# eeZeeProp.net
KiCad netlist of a schematic drawn in EAGLE
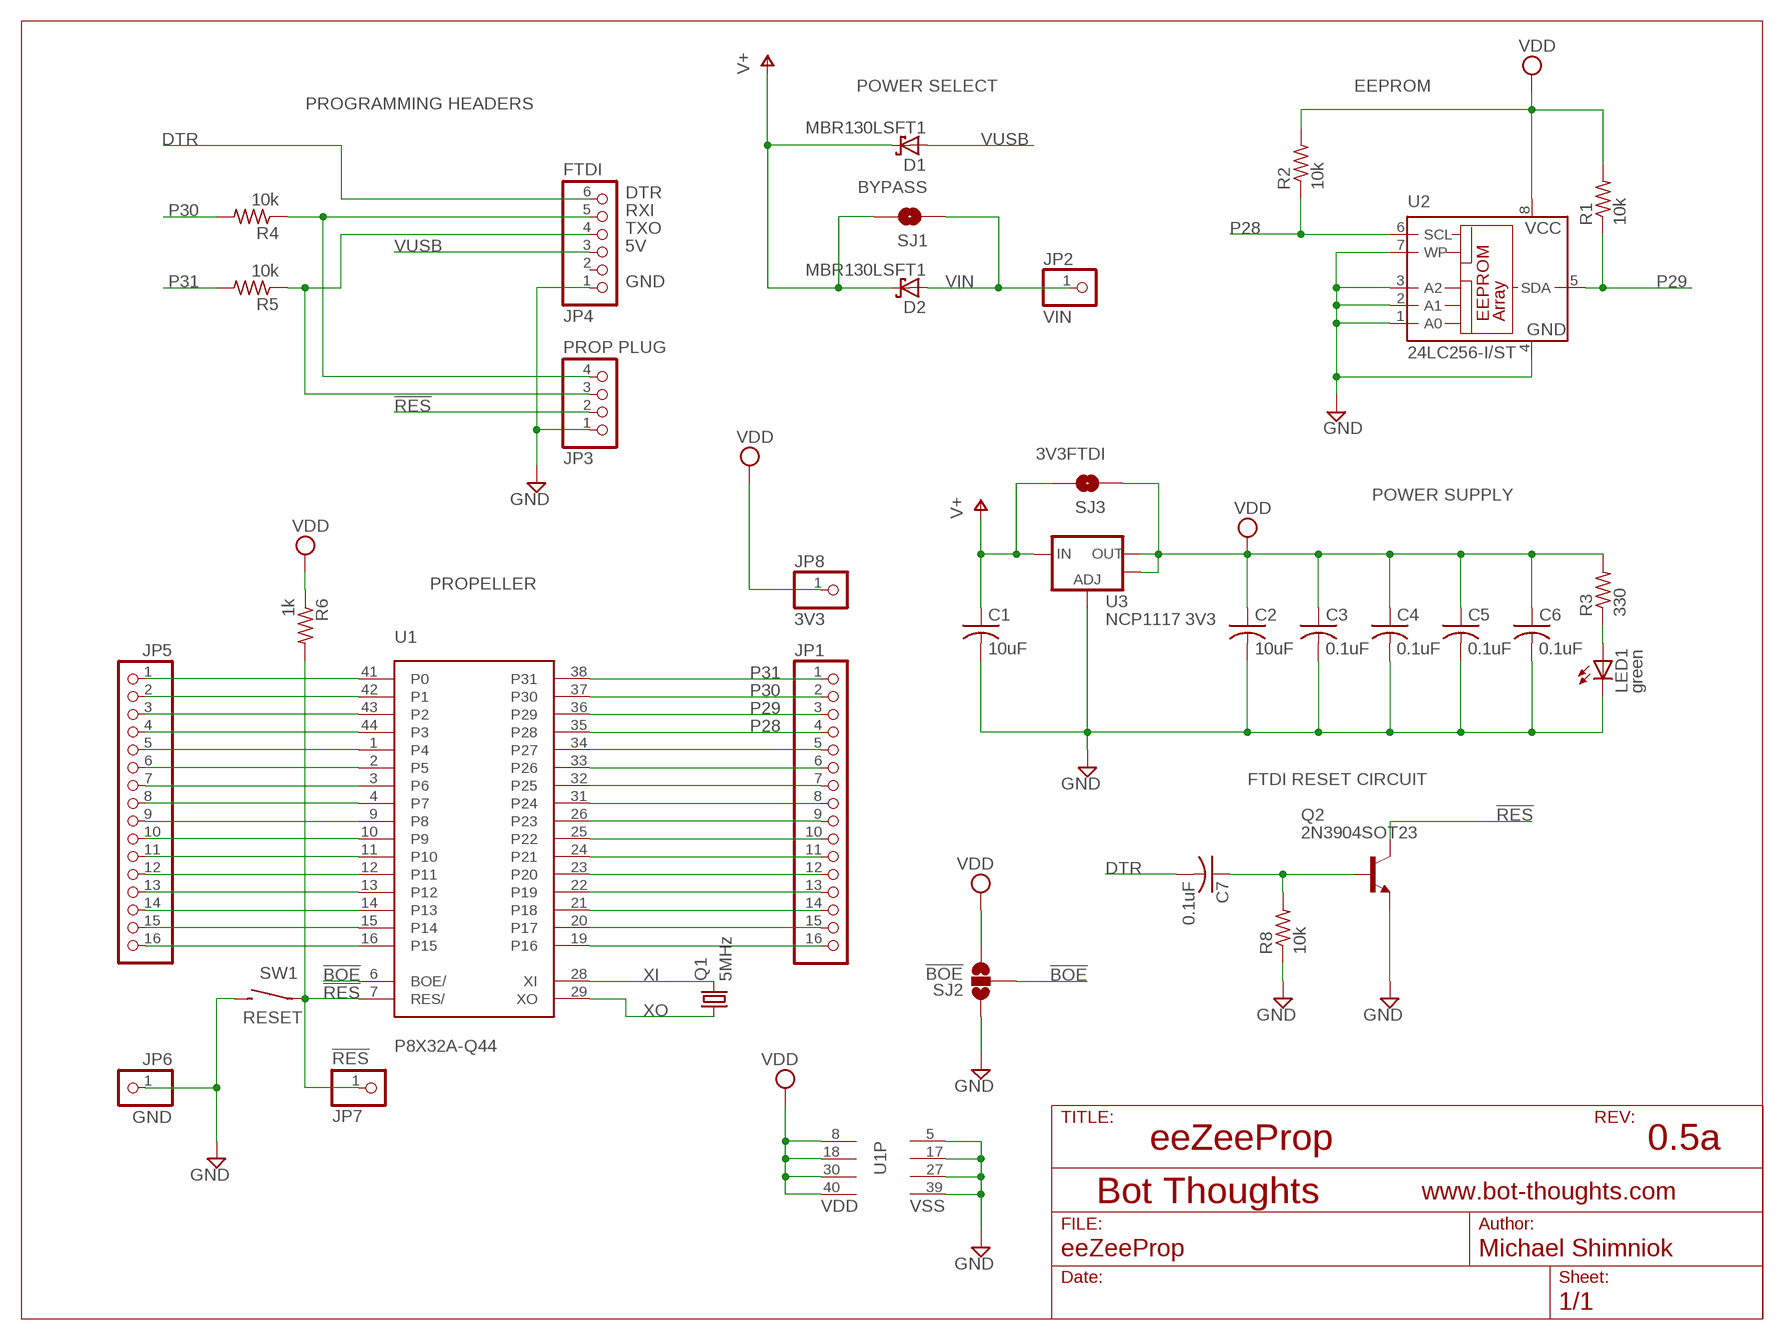
[diagram p0: schematic, sheet 1]

(export (version "E")
  (design (tool "Eeschema 10.0.6"))
  (components
    (comp (ref "C1")
      (value "10uF")
      (footprint "eagle-import:C1206")
      (fields (field (name "PARTNO") "T491A106M006AT"))
      (libsource (lib "eagle-import") (part "C-USC1206"))
    )
    (comp (ref "C2")
      (value "10uF")
      (footprint "eagle-import:C1206")
      (fields (field (name "PARTNO") "T491A106M006AT"))
      (libsource (lib "eagle-import") (part "C-USC1206"))
    )
    (comp (ref "C3")
      (value "0.1uF")
      (footprint "eagle-import:C0603")
      (fields (field (name "PARTNO") "0603YC104KAT2A"))
      (libsource (lib "eagle-import") (part "C-USC0603"))
    )
    (comp (ref "C4")
      (value "0.1uF")
      (footprint "eagle-import:C0603")
      (fields (field (name "PARTNO") "0603YC104KAT2A"))
      (libsource (lib "eagle-import") (part "C-USC0603"))
    )
    (comp (ref "C5")
      (value "0.1uF")
      (footprint "eagle-import:C0603")
      (fields (field (name "PARTNO") "0603YC104KAT2A"))
      (libsource (lib "eagle-import") (part "C-USC0603"))
    )
    (comp (ref "C6")
      (value "0.1uF")
      (footprint "eagle-import:C0603")
      (fields (field (name "PARTNO") "0603YC104KAT2A"))
      (libsource (lib "eagle-import") (part "C-USC0603"))
    )
    (comp (ref "C7")
      (value "0.1uF")
      (footprint "eagle-import:C0603")
      (fields (field (name "PARTNO") "0603YC104KAT2A"))
      (libsource (lib "eagle-import") (part "C-USC0603"))
    )
    (comp (ref "D1")
      (value "MBR130LSFT1")
      (footprint "eagle-import:SOD123FL")
      (fields (field (name "PARTNO") "MBR130LSFT1G"))
      (libsource (lib "eagle-import") (part "SCHOTTKY-DIODE-MBR130LSFT1"))
    )
    (comp (ref "D2")
      (value "MBR130LSFT1")
      (footprint "eagle-import:SOD123FL")
      (fields (field (name "PARTNO") "MBR130LSFT1G"))
      (libsource (lib "eagle-import") (part "SCHOTTKY-DIODE-MBR130LSFT1"))
    )
    (comp (ref "JP1")
      (value "PINHD-1X16_2.54-S")
      (footprint "eagle-import:1X16-S")
      (libsource (lib "eagle-import") (part "PINHD-1X16_2.54-S"))
    )
    (comp (ref "JP2")
      (value "VIN")
      (footprint "eagle-import:1X01")
      (libsource (lib "eagle-import") (part "PINHD-1X01_2.54"))
    )
    (comp (ref "JP3")
      (value "PROP PLUG")
      (footprint "eagle-import:1X04-S")
      (libsource (lib "eagle-import") (part "PINHD-1X04_2.54-S"))
    )
    (comp (ref "JP4")
      (value "FTDI")
      (footprint "eagle-import:1X06-S")
      (fields (field (name "PARTNO") "2211S-06G"))
      (libsource (lib "eagle-import") (part "PINHD-1X06_2.54-S"))
    )
    (comp (ref "JP5")
      (value "PINHD-1X16_2.54-S")
      (footprint "eagle-import:1X16-S")
      (libsource (lib "eagle-import") (part "PINHD-1X16_2.54-S"))
    )
    (comp (ref "JP6")
      (value "GND")
      (footprint "eagle-import:1X01")
      (libsource (lib "eagle-import") (part "PINHD-1X01_2.54"))
    )
    (comp (ref "JP7")
      (value "!RES")
      (footprint "eagle-import:1X01")
      (libsource (lib "eagle-import") (part "PINHD-1X01_2.54"))
    )
    (comp (ref "JP8")
      (value "3V3")
      (footprint "eagle-import:1X01")
      (libsource (lib "eagle-import") (part "PINHD-1X01_2.54"))
    )
    (comp (ref "LED1")
      (value "green")
      (footprint "eagle-import:CHIPLED_1206")
      (fields (field (name "PARTNO") "LG N971-KN-1"))
      (libsource (lib "eagle-import") (part "LEDCHIPLED_1206"))
    )
    (comp (ref "Q1")
      (value "5MHz")
      (footprint "eagle-import:HC49U-V")
      (fields (field (name "OC_FARNELL") "1666969") (field (name "PARTNO") "HC49US-5.000MABJ-UB"))
      (libsource (lib "eagle-import") (part "CRYSTALHC49U-V"))
    )
    (comp (ref "Q2")
      (value "2N3904SOT23")
      (footprint "eagle-import:SOT-23")
      (fields (field (name "PARTNO") "MMBT3904LT3G"))
      (libsource (lib "eagle-import") (part "2N3904SOT23"))
    )
    (comp (ref "R1")
      (value "10k")
      (footprint "eagle-import:R0603")
      (fields (field (name "PARTNO") "ERJ-3GEYJ103V"))
      (libsource (lib "eagle-import") (part "R-US_R0603"))
    )
    (comp (ref "R2")
      (value "10k")
      (footprint "eagle-import:R0603")
      (fields (field (name "PARTNO") "ERJ-3GEYJ103V"))
      (libsource (lib "eagle-import") (part "R-US_R0603"))
    )
    (comp (ref "R3")
      (value "330")
      (footprint "eagle-import:R0603")
      (fields (field (name "PARTNO") "ERJ-3GEYJ331V"))
      (libsource (lib "eagle-import") (part "R-US_R0603"))
    )
    (comp (ref "R4")
      (value "10k")
      (footprint "eagle-import:R0603")
      (fields (field (name "PARTNO") "RC0603JR-071KL"))
      (libsource (lib "eagle-import") (part "R-US_R0603"))
    )
    (comp (ref "R5")
      (value "10k")
      (footprint "eagle-import:R0603")
      (fields (field (name "PARTNO") "RC0603JR-071KL"))
      (libsource (lib "eagle-import") (part "R-US_R0603"))
    )
    (comp (ref "R6")
      (value "1k")
      (footprint "eagle-import:R0603")
      (fields (field (name "PARTNO") "RC0603JR-071KL"))
      (libsource (lib "eagle-import") (part "R-US_R0603"))
    )
    (comp (ref "R8")
      (value "10k")
      (footprint "eagle-import:R0603")
      (fields (field (name "PARTNO") "ERJ-3GEYJ103V"))
      (libsource (lib "eagle-import") (part "R-US_R0603"))
    )
    (comp (ref "SJ1")
      (value "BYPASS")
      (footprint "eagle-import:SJ_2S-NO")
      (libsource (lib "eagle-import") (part "SOLDERJUMPERNO"))
    )
    (comp (ref "SJ2")
      (value "!BOE")
      (footprint "eagle-import:SJ_3")
      (libsource (lib "eagle-import") (part "SOLDERJUMPER_2WAYS"))
    )
    (comp (ref "SJ3")
      (value "3V3FTDI")
      (footprint "eagle-import:SJ_2S-NO")
      (libsource (lib "eagle-import") (part "SOLDERJUMPERNO"))
    )
    (comp (ref "SW1")
      (value "RESET")
      (footprint "eagle-import:6MMTACTILE_RECT")
      (fields (field (name "PARTNO") "MJTP1243"))
      (libsource (lib "eagle-import") (part "SPST_TAC_RECT1"))
    )
    (comp (ref "U1")
      (value "P8X32A-Q44")
      (footprint "eagle-import:P8X32A-Q44")
      (fields (field (name "PARTNO") "P8X32A-Q44"))
      (libsource (lib "eagle-import") (part "P8X32A-Q44"))
    )
    (comp (ref "U2")
      (value "24LC256-I/ST")
      (footprint "eagle-import:SO-08")
      (fields
        (field (name "MF") "MICROCHIP")
        (field (name "MPN") "24LC128-I/SNG")
        (field (name "MF_1") "OnSemi")
        (field (name "MPN_1") "CAT24C256WI-GT3")
        (field (name "PARTNO") "CAT24C256WI-GT3")
      )
      (libsource (lib "eagle-import") (part "24SNLC128"))
    )
    (comp (ref "U3")
      (value "NCP1117 3V3")
      (footprint "eagle-import:SOT223")
      (fields (field (name "PARTNO") "NCP1117ST33T3G"))
      (libsource (lib "eagle-import") (part "V_REG_LM1117SOT223"))
    )
  )
  (nets
    (net (code "1") (name "/DTR") (class "Default")
      (node (ref "C7") (pin "2") (pinfunction "2_2") (pintype "passive"))
      (node (ref "JP4") (pin "6") (pinfunction "6_6") (pintype "passive"))
    )
    (net (code "2") (name "/P28") (class "Default")
      (node (ref "JP1") (pin "4") (pinfunction "4_4") (pintype "passive"))
      (node (ref "R2") (pin "1") (pinfunction "1_1") (pintype "passive"))
      (node (ref "U1") (pin "35") (pinfunction "P28_35") (pintype "bidirectional"))
      (node (ref "U2") (pin "6") (pinfunction "SCL_6") (pintype "input"))
    )
    (net (code "3") (name "/P29") (class "Default")
      (node (ref "JP1") (pin "3") (pinfunction "3_3") (pintype "passive"))
      (node (ref "R1") (pin "1") (pinfunction "1_1") (pintype "passive"))
      (node (ref "U1") (pin "36") (pinfunction "P29_36") (pintype "bidirectional"))
      (node (ref "U2") (pin "5") (pinfunction "SDA_5") (pintype "bidirectional"))
    )
    (net (code "4") (name "/P30") (class "Default")
      (node (ref "JP1") (pin "2") (pinfunction "2_2") (pintype "passive"))
      (node (ref "R4") (pin "2") (pinfunction "2_2") (pintype "passive"))
      (node (ref "U1") (pin "37") (pinfunction "P30_37") (pintype "bidirectional"))
    )
    (net (code "5") (name "/P31") (class "Default")
      (node (ref "JP1") (pin "1") (pinfunction "1_1") (pintype "passive"))
      (node (ref "R5") (pin "2") (pinfunction "2_2") (pintype "passive"))
      (node (ref "U1") (pin "38") (pinfunction "P31_38") (pintype "bidirectional"))
    )
    (net (code "6") (name "/VIN") (class "Default")
      (node (ref "D2") (pin "A") (pinfunction "A_A") (pintype "passive"))
      (node (ref "JP2") (pin "1") (pinfunction "1_1") (pintype "passive"))
      (node (ref "SJ1") (pin "1") (pinfunction "1_1") (pintype "passive"))
    )
    (net (code "7") (name "/VUSB") (class "Default")
      (node (ref "D1") (pin "A") (pinfunction "A_A") (pintype "passive"))
      (node (ref "JP4") (pin "3") (pinfunction "3_3") (pintype "passive"))
    )
    (net (code "8") (name "/XI") (class "Default")
      (node (ref "Q1") (pin "2") (pinfunction "2_2") (pintype "passive"))
      (node (ref "U1") (pin "28") (pinfunction "XI_28") (pintype "input"))
    )
    (net (code "9") (name "/XO") (class "Default")
      (node (ref "Q1") (pin "1") (pinfunction "1_1") (pintype "passive"))
      (node (ref "U1") (pin "29") (pinfunction "XO_29") (pintype "output"))
    )
    (net (code "10") (name "/~{BOE}") (class "Default")
      (node (ref "SJ2") (pin "2") (pinfunction "2_2") (pintype "passive"))
      (node (ref "U1") (pin "6") (pinfunction "BOE/_6") (pintype "input"))
    )
    (net (code "11") (name "/~{RES}") (class "Default")
      (node (ref "JP3") (pin "2") (pinfunction "2_2") (pintype "passive"))
      (node (ref "JP7") (pin "1") (pinfunction "1_1") (pintype "passive"))
      (node (ref "Q2") (pin "1") (pinfunction "C_1") (pintype "passive"))
      (node (ref "R6") (pin "2") (pinfunction "2_2") (pintype "passive"))
      (node (ref "SW1") (pin "P$1") (pinfunction "P_P$1") (pintype "passive"))
      (node (ref "U1") (pin "7") (pinfunction "RES/_7") (pintype "bidirectional"))
    )
    (net (code "12") (name "GND") (class "Default")
      (node (ref "C1") (pin "2") (pinfunction "2_2") (pintype "passive"))
      (node (ref "C2") (pin "2") (pinfunction "2_2") (pintype "passive"))
      (node (ref "C3") (pin "2") (pinfunction "2_2") (pintype "passive"))
      (node (ref "C4") (pin "2") (pinfunction "2_2") (pintype "passive"))
      (node (ref "C5") (pin "2") (pinfunction "2_2") (pintype "passive"))
      (node (ref "C6") (pin "2") (pinfunction "2_2") (pintype "passive"))
      (node (ref "JP3") (pin "1") (pinfunction "1_1") (pintype "passive"))
      (node (ref "JP4") (pin "1") (pinfunction "1_1") (pintype "passive"))
      (node (ref "JP6") (pin "1") (pinfunction "1_1") (pintype "passive"))
      (node (ref "LED1") (pin "C") (pinfunction "C_C") (pintype "passive"))
      (node (ref "Q2") (pin "2") (pinfunction "E_2") (pintype "passive"))
      (node (ref "R8") (pin "1") (pinfunction "1_1") (pintype "passive"))
      (node (ref "SJ2") (pin "1") (pinfunction "1_1") (pintype "passive"))
      (node (ref "SW1") (pin "P$2") (pinfunction "S_P$2") (pintype "passive"))
      (node (ref "U1") (pin "17") (pinfunction "VSS_17") (pintype "power_in"))
      (node (ref "U1") (pin "27") (pinfunction "VSS_27") (pintype "power_in"))
      (node (ref "U1") (pin "39") (pinfunction "VSS_39") (pintype "power_in"))
      (node (ref "U1") (pin "5") (pinfunction "VSS_5") (pintype "power_in"))
      (node (ref "U2") (pin "1") (pinfunction "A0_1") (pintype "input"))
      (node (ref "U2") (pin "2") (pinfunction "A1_2") (pintype "input"))
      (node (ref "U2") (pin "3") (pinfunction "A2_3") (pintype "input"))
      (node (ref "U2") (pin "4") (pinfunction "GND_4") (pintype "power_in"))
      (node (ref "U2") (pin "7") (pinfunction "WP_7") (pintype "input"))
      (node (ref "U3") (pin "1") (pinfunction "ADJ_1") (pintype "input"))
    )
    (net (code "13") (name "Net-(JP3-Pad3)") (class "Default")
      (node (ref "JP3") (pin "3") (pinfunction "3_3") (pintype "passive"))
      (node (ref "JP4") (pin "4") (pinfunction "4_4") (pintype "passive"))
      (node (ref "R5") (pin "1") (pinfunction "1_1") (pintype "passive"))
    )
    (net (code "14") (name "Net-(JP3-Pad4)") (class "Default")
      (node (ref "JP3") (pin "4") (pinfunction "4_4") (pintype "passive"))
      (node (ref "JP4") (pin "5") (pinfunction "5_5") (pintype "passive"))
      (node (ref "R4") (pin "1") (pinfunction "1_1") (pintype "passive"))
    )
    (net (code "15") (name "Net-(LED1-PadA)") (class "Default")
      (node (ref "LED1") (pin "A") (pinfunction "A_A") (pintype "passive"))
      (node (ref "R3") (pin "1") (pinfunction "1_1") (pintype "passive"))
    )
    (net (code "16") (name "Net-(Q2-B)") (class "Default")
      (node (ref "C7") (pin "1") (pinfunction "1_1") (pintype "passive"))
      (node (ref "Q2") (pin "3") (pinfunction "B_3") (pintype "passive"))
      (node (ref "R8") (pin "2") (pinfunction "2_2") (pintype "passive"))
    )
    (net (code "17") (name "Net-(U1B-P0)") (class "Default")
      (node (ref "JP5") (pin "1") (pinfunction "1_1") (pintype "passive"))
      (node (ref "U1") (pin "41") (pinfunction "P0_41") (pintype "bidirectional"))
    )
    (net (code "18") (name "Net-(U1B-P1)") (class "Default")
      (node (ref "JP5") (pin "2") (pinfunction "2_2") (pintype "passive"))
      (node (ref "U1") (pin "42") (pinfunction "P1_42") (pintype "bidirectional"))
    )
    (net (code "19") (name "Net-(U1B-P2)") (class "Default")
      (node (ref "JP5") (pin "3") (pinfunction "3_3") (pintype "passive"))
      (node (ref "U1") (pin "43") (pinfunction "P2_43") (pintype "bidirectional"))
    )
    (net (code "20") (name "Net-(U1B-P3)") (class "Default")
      (node (ref "JP5") (pin "4") (pinfunction "4_4") (pintype "passive"))
      (node (ref "U1") (pin "44") (pinfunction "P3_44") (pintype "bidirectional"))
    )
    (net (code "21") (name "Net-(U1B-P4)") (class "Default")
      (node (ref "JP5") (pin "5") (pinfunction "5_5") (pintype "passive"))
      (node (ref "U1") (pin "1") (pinfunction "P4_1") (pintype "bidirectional"))
    )
    (net (code "22") (name "Net-(U1B-P5)") (class "Default")
      (node (ref "JP5") (pin "6") (pinfunction "6_6") (pintype "passive"))
      (node (ref "U1") (pin "2") (pinfunction "P5_2") (pintype "bidirectional"))
    )
    (net (code "23") (name "Net-(U1B-P6)") (class "Default")
      (node (ref "JP5") (pin "7") (pinfunction "7_7") (pintype "passive"))
      (node (ref "U1") (pin "3") (pinfunction "P6_3") (pintype "bidirectional"))
    )
    (net (code "24") (name "Net-(U1B-P7)") (class "Default")
      (node (ref "JP5") (pin "8") (pinfunction "8_8") (pintype "passive"))
      (node (ref "U1") (pin "4") (pinfunction "P7_4") (pintype "bidirectional"))
    )
    (net (code "25") (name "Net-(U1B-P8)") (class "Default")
      (node (ref "JP5") (pin "9") (pinfunction "9_9") (pintype "passive"))
      (node (ref "U1") (pin "9") (pinfunction "P8_9") (pintype "bidirectional"))
    )
    (net (code "26") (name "Net-(U1B-P9)") (class "Default")
      (node (ref "JP5") (pin "10") (pinfunction "10_10") (pintype "passive"))
      (node (ref "U1") (pin "10") (pinfunction "P9_10") (pintype "bidirectional"))
    )
    (net (code "27") (name "Net-(U1B-P10)") (class "Default")
      (node (ref "JP5") (pin "11") (pinfunction "11_11") (pintype "passive"))
      (node (ref "U1") (pin "11") (pinfunction "P10_11") (pintype "bidirectional"))
    )
    (net (code "28") (name "Net-(U1B-P11)") (class "Default")
      (node (ref "JP5") (pin "12") (pinfunction "12_12") (pintype "passive"))
      (node (ref "U1") (pin "12") (pinfunction "P11_12") (pintype "bidirectional"))
    )
    (net (code "29") (name "Net-(U1B-P12)") (class "Default")
      (node (ref "JP5") (pin "13") (pinfunction "13_13") (pintype "passive"))
      (node (ref "U1") (pin "13") (pinfunction "P12_13") (pintype "bidirectional"))
    )
    (net (code "30") (name "Net-(U1B-P13)") (class "Default")
      (node (ref "JP5") (pin "14") (pinfunction "14_14") (pintype "passive"))
      (node (ref "U1") (pin "14") (pinfunction "P13_14") (pintype "bidirectional"))
    )
    (net (code "31") (name "Net-(U1B-P14)") (class "Default")
      (node (ref "JP5") (pin "15") (pinfunction "15_15") (pintype "passive"))
      (node (ref "U1") (pin "15") (pinfunction "P14_15") (pintype "bidirectional"))
    )
    (net (code "32") (name "Net-(U1B-P15)") (class "Default")
      (node (ref "JP5") (pin "16") (pinfunction "16_16") (pintype "passive"))
      (node (ref "U1") (pin "16") (pinfunction "P15_16") (pintype "bidirectional"))
    )
    (net (code "33") (name "Net-(U1B-P16)") (class "Default")
      (node (ref "JP1") (pin "16") (pinfunction "16_16") (pintype "passive"))
      (node (ref "U1") (pin "19") (pinfunction "P16_19") (pintype "bidirectional"))
    )
    (net (code "34") (name "Net-(U1B-P17)") (class "Default")
      (node (ref "JP1") (pin "15") (pinfunction "15_15") (pintype "passive"))
      (node (ref "U1") (pin "20") (pinfunction "P17_20") (pintype "bidirectional"))
    )
    (net (code "35") (name "Net-(U1B-P18)") (class "Default")
      (node (ref "JP1") (pin "14") (pinfunction "14_14") (pintype "passive"))
      (node (ref "U1") (pin "21") (pinfunction "P18_21") (pintype "bidirectional"))
    )
    (net (code "36") (name "Net-(U1B-P19)") (class "Default")
      (node (ref "JP1") (pin "13") (pinfunction "13_13") (pintype "passive"))
      (node (ref "U1") (pin "22") (pinfunction "P19_22") (pintype "bidirectional"))
    )
    (net (code "37") (name "Net-(U1B-P20)") (class "Default")
      (node (ref "JP1") (pin "12") (pinfunction "12_12") (pintype "passive"))
      (node (ref "U1") (pin "23") (pinfunction "P20_23") (pintype "bidirectional"))
    )
    (net (code "38") (name "Net-(U1B-P21)") (class "Default")
      (node (ref "JP1") (pin "11") (pinfunction "11_11") (pintype "passive"))
      (node (ref "U1") (pin "24") (pinfunction "P21_24") (pintype "bidirectional"))
    )
    (net (code "39") (name "Net-(U1B-P22)") (class "Default")
      (node (ref "JP1") (pin "10") (pinfunction "10_10") (pintype "passive"))
      (node (ref "U1") (pin "25") (pinfunction "P22_25") (pintype "bidirectional"))
    )
    (net (code "40") (name "Net-(U1B-P23)") (class "Default")
      (node (ref "JP1") (pin "9") (pinfunction "9_9") (pintype "passive"))
      (node (ref "U1") (pin "26") (pinfunction "P23_26") (pintype "bidirectional"))
    )
    (net (code "41") (name "Net-(U1B-P24)") (class "Default")
      (node (ref "JP1") (pin "8") (pinfunction "8_8") (pintype "passive"))
      (node (ref "U1") (pin "31") (pinfunction "P24_31") (pintype "bidirectional"))
    )
    (net (code "42") (name "Net-(U1B-P25)") (class "Default")
      (node (ref "JP1") (pin "7") (pinfunction "7_7") (pintype "passive"))
      (node (ref "U1") (pin "32") (pinfunction "P25_32") (pintype "bidirectional"))
    )
    (net (code "43") (name "Net-(U1B-P26)") (class "Default")
      (node (ref "JP1") (pin "6") (pinfunction "6_6") (pintype "passive"))
      (node (ref "U1") (pin "33") (pinfunction "P26_33") (pintype "bidirectional"))
    )
    (net (code "44") (name "Net-(U1B-P27)") (class "Default")
      (node (ref "JP1") (pin "5") (pinfunction "5_5") (pintype "passive"))
      (node (ref "U1") (pin "34") (pinfunction "P27_34") (pintype "bidirectional"))
    )
    (net (code "45") (name "V+") (class "Default")
      (node (ref "C1") (pin "1") (pinfunction "1_1") (pintype "passive"))
      (node (ref "D1") (pin "C") (pinfunction "C_C") (pintype "passive"))
      (node (ref "D2") (pin "C") (pinfunction "C_C") (pintype "passive"))
      (node (ref "SJ1") (pin "2") (pinfunction "2_2") (pintype "passive"))
      (node (ref "SJ3") (pin "2") (pinfunction "2_2") (pintype "passive"))
      (node (ref "U3") (pin "3") (pinfunction "IN_3") (pintype "input"))
    )
    (net (code "46") (name "VDD") (class "Default")
      (node (ref "C2") (pin "1") (pinfunction "1_1") (pintype "passive"))
      (node (ref "C3") (pin "1") (pinfunction "1_1") (pintype "passive"))
      (node (ref "C4") (pin "1") (pinfunction "1_1") (pintype "passive"))
      (node (ref "C5") (pin "1") (pinfunction "1_1") (pintype "passive"))
      (node (ref "C6") (pin "1") (pinfunction "1_1") (pintype "passive"))
      (node (ref "JP8") (pin "1") (pinfunction "1_1") (pintype "passive"))
      (node (ref "R1") (pin "2") (pinfunction "2_2") (pintype "passive"))
      (node (ref "R2") (pin "2") (pinfunction "2_2") (pintype "passive"))
      (node (ref "R3") (pin "2") (pinfunction "2_2") (pintype "passive"))
      (node (ref "R6") (pin "1") (pinfunction "1_1") (pintype "passive"))
      (node (ref "SJ2") (pin "3") (pinfunction "3_3") (pintype "passive"))
      (node (ref "SJ3") (pin "1") (pinfunction "1_1") (pintype "passive"))
      (node (ref "U1") (pin "18") (pinfunction "VDD_18") (pintype "power_in"))
      (node (ref "U1") (pin "30") (pinfunction "VDD_30") (pintype "power_in"))
      (node (ref "U1") (pin "40") (pinfunction "VDD_40") (pintype "power_in"))
      (node (ref "U1") (pin "8") (pinfunction "VDD_8") (pintype "power_in"))
      (node (ref "U2") (pin "8") (pinfunction "VCC_8") (pintype "power_in"))
      (node (ref "U3") (pin "2") (pinfunction "OUT_2") (pintype "output"))
      (node (ref "U3") (pin "4") (pinfunction "OUT_4") (pintype "output"))
    )
    (net (code "47") (name "unconnected-(JP4-Pad2)") (class "Default")
      (node (ref "JP4") (pin "2") (pinfunction "2_2") (pintype "passive"))
    )
  )
)
